# gyrotestbench.net
KiCad netlist of a schematic drawn in EAGLE
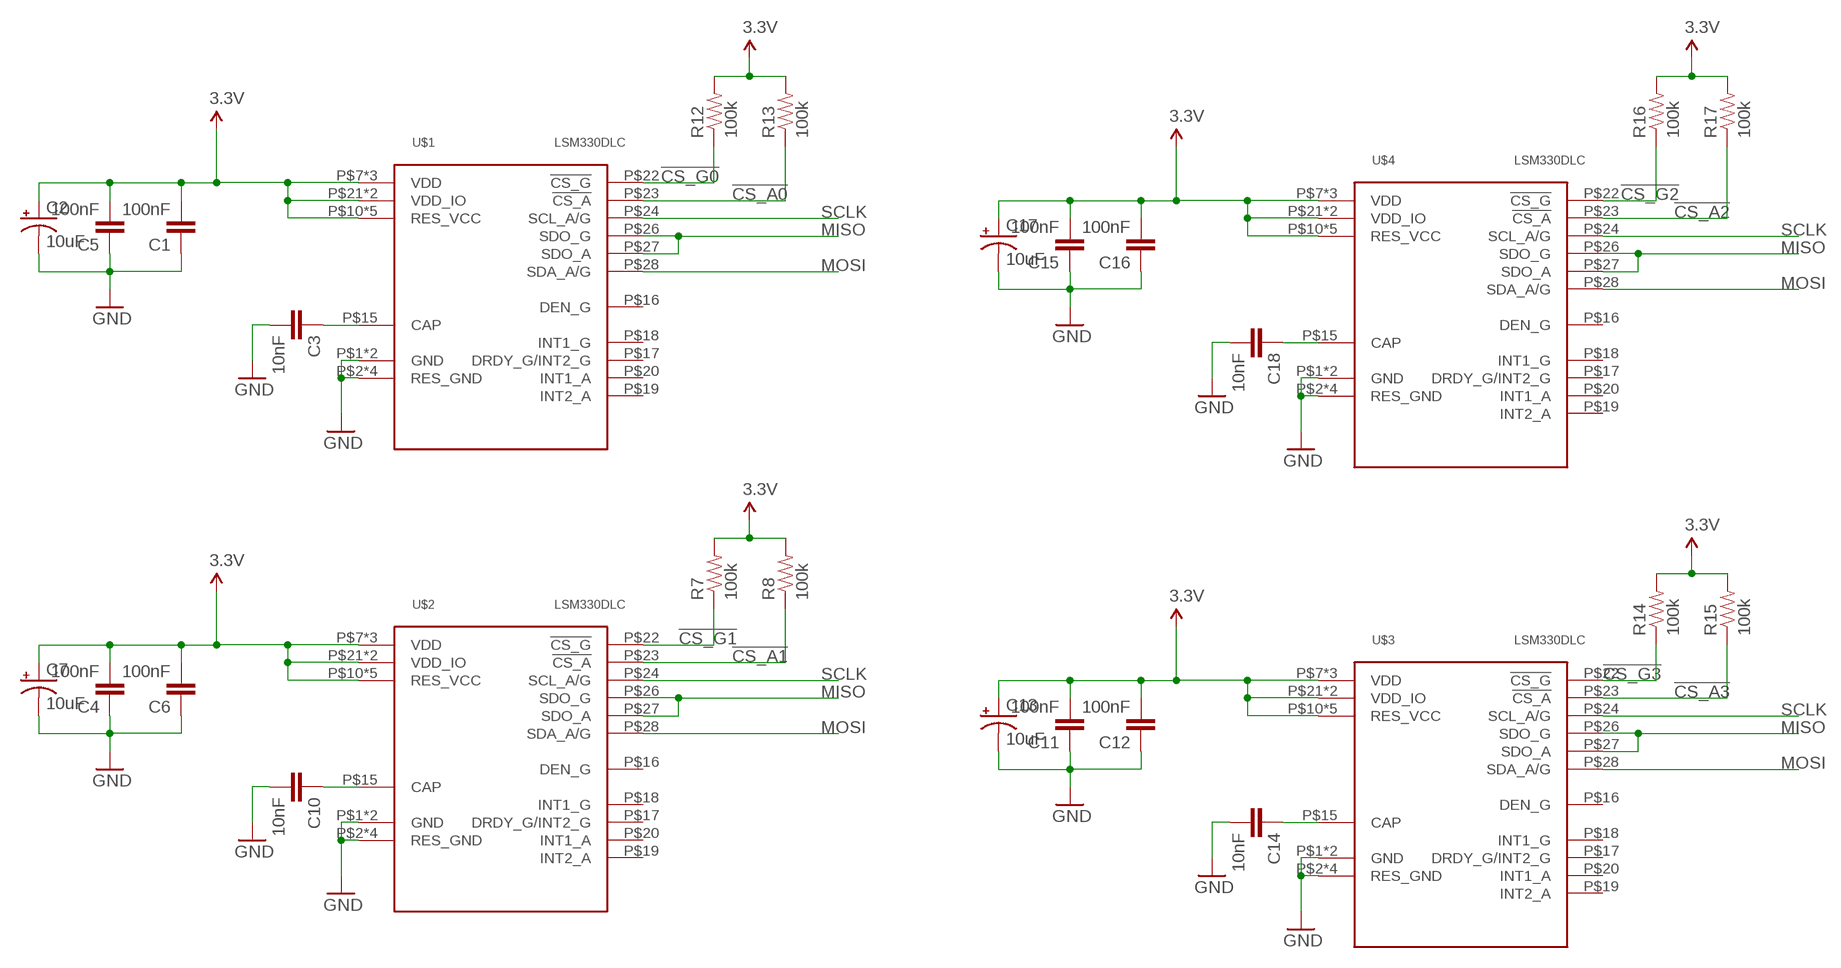
[diagram p0: schematic, sheet 1]
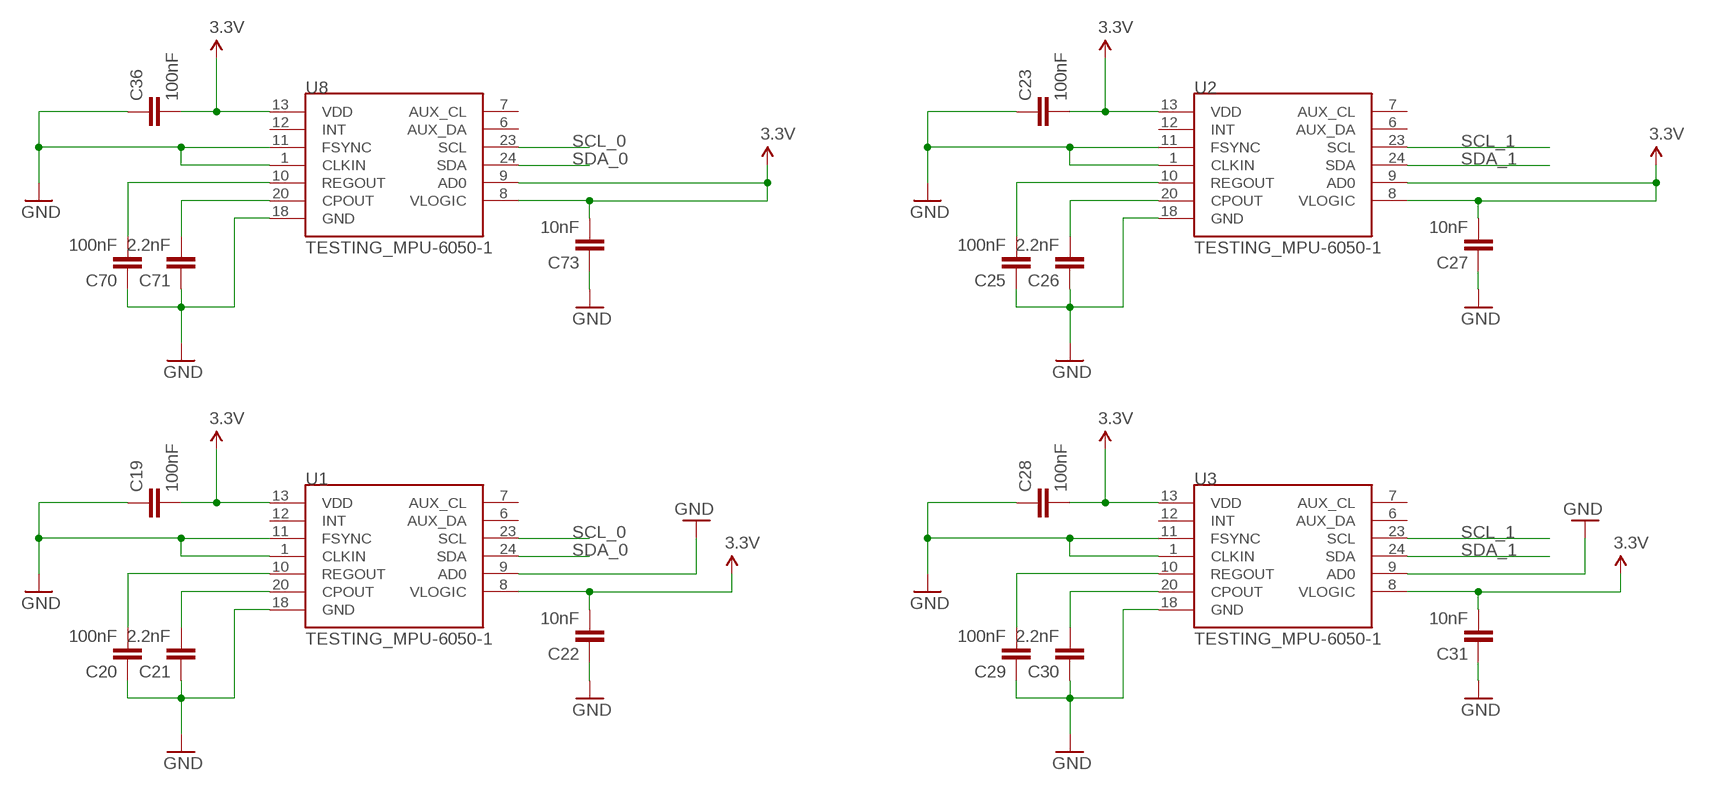
[diagram p1: schematic, sheet 2]
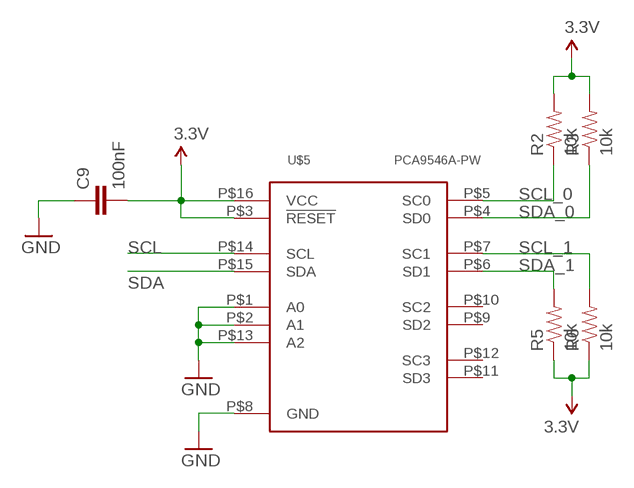
[diagram p2: schematic, sheet 3]
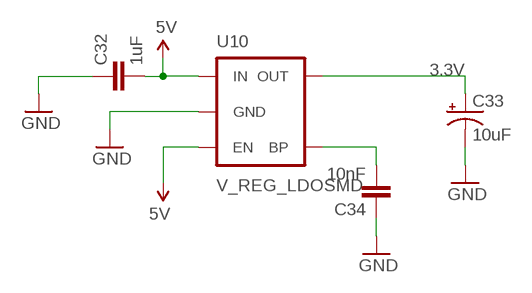
[diagram p3: schematic, sheet 4]
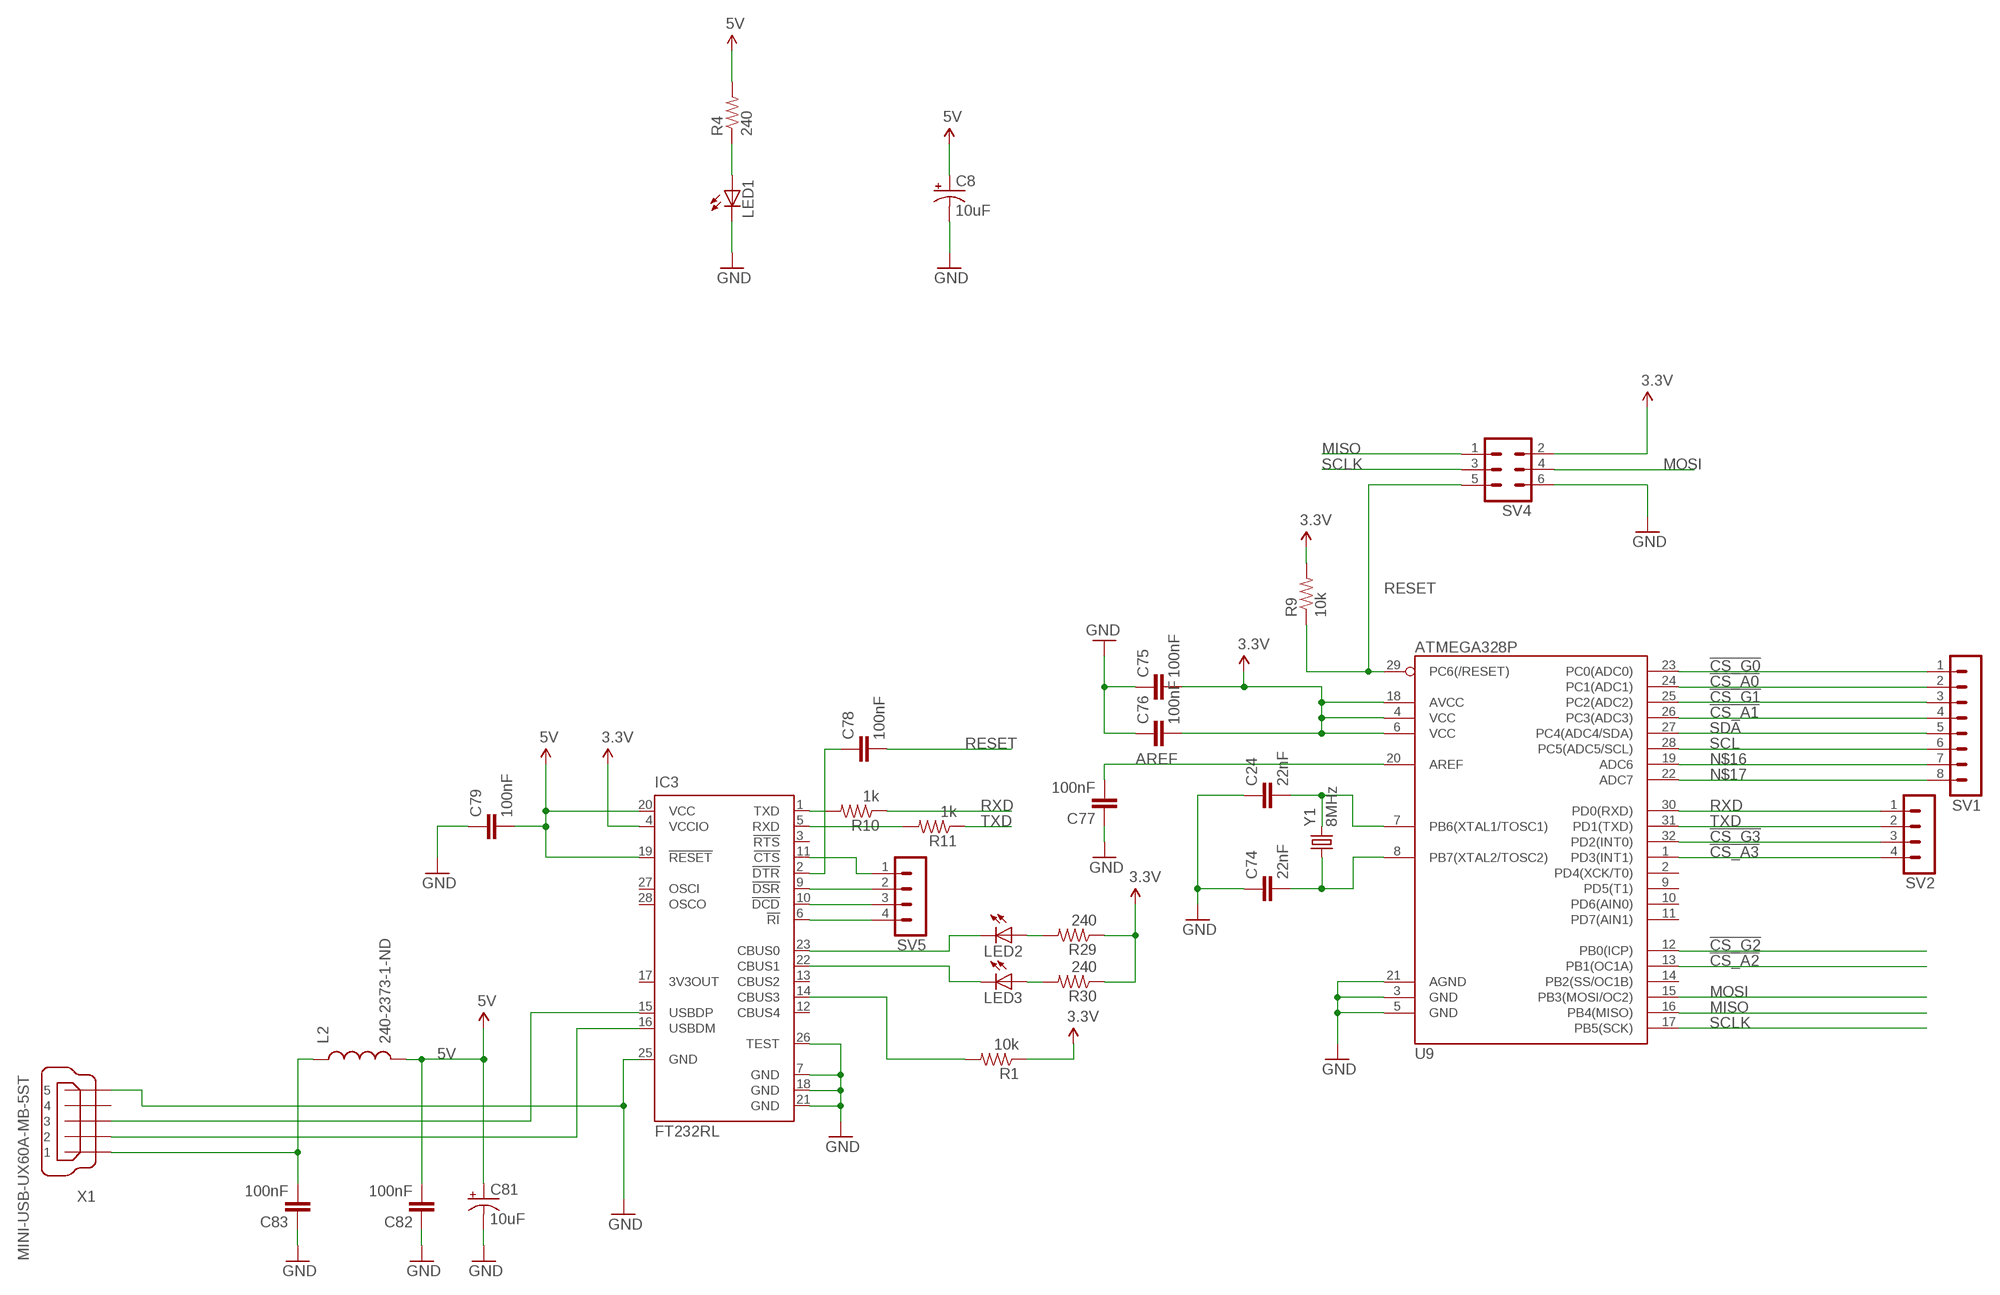
[diagram p4: schematic, sheet 5]

(export (version "E")
  (design (tool "Eeschema 10.0.6"))
  (components
    (comp (ref "C19")
      (value "100nF")
      (footprint "eagle-import:0603-CAP")
      (libsource (lib "eagle-import") (part "CAP0603-CAP"))
    )
    (comp (ref "C20")
      (value "100nF")
      (footprint "eagle-import:0603-CAP")
      (libsource (lib "eagle-import") (part "CAP0603-CAP"))
    )
    (comp (ref "C21")
      (value "2.2nF")
      (footprint "eagle-import:0603-CAP")
      (libsource (lib "eagle-import") (part "CAP0603-CAP"))
    )
    (comp (ref "C22")
      (value "10nF")
      (footprint "eagle-import:0603-CAP")
      (libsource (lib "eagle-import") (part "CAP0603-CAP"))
    )
    (comp (ref "C23")
      (value "100nF")
      (footprint "eagle-import:0603-CAP")
      (libsource (lib "eagle-import") (part "CAP0603-CAP"))
    )
    (comp (ref "C25")
      (value "100nF")
      (footprint "eagle-import:0603-CAP")
      (libsource (lib "eagle-import") (part "CAP0603-CAP"))
    )
    (comp (ref "C26")
      (value "2.2nF")
      (footprint "eagle-import:0603-CAP")
      (libsource (lib "eagle-import") (part "CAP0603-CAP"))
    )
    (comp (ref "C27")
      (value "10nF")
      (footprint "eagle-import:0603-CAP")
      (libsource (lib "eagle-import") (part "CAP0603-CAP"))
    )
    (comp (ref "C28")
      (value "100nF")
      (footprint "eagle-import:0603-CAP")
      (libsource (lib "eagle-import") (part "CAP0603-CAP"))
    )
    (comp (ref "C29")
      (value "100nF")
      (footprint "eagle-import:0603-CAP")
      (libsource (lib "eagle-import") (part "CAP0603-CAP"))
    )
    (comp (ref "C30")
      (value "2.2nF")
      (footprint "eagle-import:0603-CAP")
      (libsource (lib "eagle-import") (part "CAP0603-CAP"))
    )
    (comp (ref "C31")
      (value "10nF")
      (footprint "eagle-import:0603-CAP")
      (libsource (lib "eagle-import") (part "CAP0603-CAP"))
    )
    (comp (ref "C36")
      (value "100nF")
      (footprint "eagle-import:0603-CAP")
      (libsource (lib "eagle-import") (part "CAP0603-CAP"))
    )
    (comp (ref "C70")
      (value "100nF")
      (footprint "eagle-import:0603-CAP")
      (libsource (lib "eagle-import") (part "CAP0603-CAP"))
    )
    (comp (ref "C71")
      (value "2.2nF")
      (footprint "eagle-import:0603-CAP")
      (libsource (lib "eagle-import") (part "CAP0603-CAP"))
    )
    (comp (ref "C73")
      (value "10nF")
      (footprint "eagle-import:0603-CAP")
      (libsource (lib "eagle-import") (part "CAP0603-CAP"))
    )
    (comp (ref "U1")
      (value "TESTING_MPU-6050-1")
      (footprint "eagle-import:TESTING_QFN-24-4MM2")
      (libsource (lib "eagle-import") (part "TESTING_MPU-6050-1"))
    )
    (comp (ref "U2")
      (value "TESTING_MPU-6050-1")
      (footprint "eagle-import:TESTING_QFN-24-4MM2")
      (libsource (lib "eagle-import") (part "TESTING_MPU-6050-1"))
    )
    (comp (ref "U3")
      (value "TESTING_MPU-6050-1")
      (footprint "eagle-import:TESTING_QFN-24-4MM2")
      (libsource (lib "eagle-import") (part "TESTING_MPU-6050-1"))
    )
    (comp (ref "U8")
      (value "TESTING_MPU-6050-1")
      (footprint "eagle-import:TESTING_QFN-24-4MM2")
      (libsource (lib "eagle-import") (part "TESTING_MPU-6050-1"))
    )
    (comp (ref "C32")
      (value "1uF")
      (footprint "eagle-import:0603-CAP")
      (libsource (lib "eagle-import") (part "CAP0603-CAP"))
    )
    (comp (ref "C33")
      (value "10uF")
      (footprint "eagle-import:PANASONIC_B")
      (libsource (lib "eagle-import") (part "CPOL-USB"))
    )
    (comp (ref "C34")
      (value "10nF")
      (footprint "eagle-import:0603-CAP")
      (libsource (lib "eagle-import") (part "CAP0603-CAP"))
    )
    (comp (ref "U10")
      (value "V_REG_LDOSMD")
      (footprint "eagle-import:SOT23-5")
      (libsource (lib "eagle-import") (part "V_REG_LDOSMD"))
    )
    (comp (ref "C1")
      (value "100nF")
      (footprint "eagle-import:0603-CAP")
      (libsource (lib "eagle-import") (part "CAP0603-CAP"))
    )
    (comp (ref "C2")
      (value "10uF")
      (footprint "eagle-import:PANASONIC_B")
      (libsource (lib "eagle-import") (part "CPOL-USB"))
    )
    (comp (ref "C3")
      (value "10nF")
      (footprint "eagle-import:0603-CAP")
      (libsource (lib "eagle-import") (part "CAP0603-CAP"))
    )
    (comp (ref "C4")
      (value "100nF")
      (footprint "eagle-import:0603-CAP")
      (libsource (lib "eagle-import") (part "CAP0603-CAP"))
    )
    (comp (ref "C5")
      (value "100nF")
      (footprint "eagle-import:0603-CAP")
      (libsource (lib "eagle-import") (part "CAP0603-CAP"))
    )
    (comp (ref "C6")
      (value "100nF")
      (footprint "eagle-import:0603-CAP")
      (libsource (lib "eagle-import") (part "CAP0603-CAP"))
    )
    (comp (ref "C7")
      (value "10uF")
      (footprint "eagle-import:PANASONIC_B")
      (libsource (lib "eagle-import") (part "CPOL-USB"))
    )
    (comp (ref "C10")
      (value "10nF")
      (footprint "eagle-import:0603-CAP")
      (libsource (lib "eagle-import") (part "CAP0603-CAP"))
    )
    (comp (ref "C11")
      (value "100nF")
      (footprint "eagle-import:0603-CAP")
      (libsource (lib "eagle-import") (part "CAP0603-CAP"))
    )
    (comp (ref "C12")
      (value "100nF")
      (footprint "eagle-import:0603-CAP")
      (libsource (lib "eagle-import") (part "CAP0603-CAP"))
    )
    (comp (ref "C13")
      (value "10uF")
      (footprint "eagle-import:PANASONIC_B")
      (libsource (lib "eagle-import") (part "CPOL-USB"))
    )
    (comp (ref "C14")
      (value "10nF")
      (footprint "eagle-import:0603-CAP")
      (libsource (lib "eagle-import") (part "CAP0603-CAP"))
    )
    (comp (ref "C15")
      (value "100nF")
      (footprint "eagle-import:0603-CAP")
      (libsource (lib "eagle-import") (part "CAP0603-CAP"))
    )
    (comp (ref "C16")
      (value "100nF")
      (footprint "eagle-import:0603-CAP")
      (libsource (lib "eagle-import") (part "CAP0603-CAP"))
    )
    (comp (ref "C17")
      (value "10uF")
      (footprint "eagle-import:PANASONIC_B")
      (libsource (lib "eagle-import") (part "CPOL-USB"))
    )
    (comp (ref "C18")
      (value "10nF")
      (footprint "eagle-import:0603-CAP")
      (libsource (lib "eagle-import") (part "CAP0603-CAP"))
    )
    (comp (ref "R7")
      (value "100k")
      (footprint "eagle-import:0603-RES")
      (libsource (lib "eagle-import") (part "RESISTOR0603-RES"))
    )
    (comp (ref "R8")
      (value "100k")
      (footprint "eagle-import:0603-RES")
      (libsource (lib "eagle-import") (part "RESISTOR0603-RES"))
    )
    (comp (ref "R12")
      (value "100k")
      (footprint "eagle-import:0603-RES")
      (libsource (lib "eagle-import") (part "RESISTOR0603-RES"))
    )
    (comp (ref "R13")
      (value "100k")
      (footprint "eagle-import:0603-RES")
      (libsource (lib "eagle-import") (part "RESISTOR0603-RES"))
    )
    (comp (ref "R14")
      (value "100k")
      (footprint "eagle-import:0603-RES")
      (libsource (lib "eagle-import") (part "RESISTOR0603-RES"))
    )
    (comp (ref "R15")
      (value "100k")
      (footprint "eagle-import:0603-RES")
      (libsource (lib "eagle-import") (part "RESISTOR0603-RES"))
    )
    (comp (ref "R16")
      (value "100k")
      (footprint "eagle-import:0603-RES")
      (libsource (lib "eagle-import") (part "RESISTOR0603-RES"))
    )
    (comp (ref "R17")
      (value "100k")
      (footprint "eagle-import:0603-RES")
      (libsource (lib "eagle-import") (part "RESISTOR0603-RES"))
    )
    (comp (ref "U$1")
      (value "LSM330DLC")
      (footprint "eagle-import:LGA-28")
      (libsource (lib "eagle-import") (part "LSM330DLC"))
    )
    (comp (ref "U$2")
      (value "LSM330DLC")
      (footprint "eagle-import:LGA-28")
      (libsource (lib "eagle-import") (part "LSM330DLC"))
    )
    (comp (ref "U$3")
      (value "LSM330DLC")
      (footprint "eagle-import:LGA-28")
      (libsource (lib "eagle-import") (part "LSM330DLC"))
    )
    (comp (ref "U$4")
      (value "LSM330DLC")
      (footprint "eagle-import:LGA-28")
      (libsource (lib "eagle-import") (part "LSM330DLC"))
    )
    (comp (ref "C8")
      (value "10uF")
      (footprint "eagle-import:PANASONIC_B")
      (libsource (lib "eagle-import") (part "CPOL-USB"))
    )
    (comp (ref "C24")
      (value "22nF")
      (footprint "eagle-import:0603-CAP")
      (libsource (lib "eagle-import") (part "CAP0603-CAP"))
    )
    (comp (ref "C74")
      (value "22nF")
      (footprint "eagle-import:0603-CAP")
      (libsource (lib "eagle-import") (part "CAP0603-CAP"))
    )
    (comp (ref "C75")
      (value "100nF")
      (footprint "eagle-import:0603-CAP")
      (libsource (lib "eagle-import") (part "CAP0603-CAP"))
    )
    (comp (ref "C76")
      (value "100nF")
      (footprint "eagle-import:0603-CAP")
      (libsource (lib "eagle-import") (part "CAP0603-CAP"))
    )
    (comp (ref "C77")
      (value "100nF")
      (footprint "eagle-import:0603-CAP")
      (libsource (lib "eagle-import") (part "CAP0603-CAP"))
    )
    (comp (ref "C78")
      (value "100nF")
      (footprint "eagle-import:0603-CAP")
      (libsource (lib "eagle-import") (part "CAP0603-CAP"))
    )
    (comp (ref "C79")
      (value "100nF")
      (footprint "eagle-import:0603-CAP")
      (libsource (lib "eagle-import") (part "CAP0603-CAP"))
    )
    (comp (ref "C81")
      (value "10uF")
      (footprint "eagle-import:PANASONIC_B")
      (libsource (lib "eagle-import") (part "CPOL-USB"))
    )
    (comp (ref "C82")
      (value "100nF")
      (footprint "eagle-import:0603-CAP")
      (libsource (lib "eagle-import") (part "CAP0603-CAP"))
    )
    (comp (ref "C83")
      (value "100nF")
      (footprint "eagle-import:0603-CAP")
      (libsource (lib "eagle-import") (part "CAP0603-CAP"))
    )
    (comp (ref "IC3")
      (value "FT232RL")
      (footprint "eagle-import:SSOP28")
      (libsource (lib "eagle-import") (part "FT232RL"))
    )
    (comp (ref "L2")
      (value "240-2373-1-ND")
      (footprint "eagle-import:0603")
      (libsource (lib "eagle-import") (part "INDUCTOR0603"))
    )
    (comp (ref "LED1")
      (value "LED0603")
      (footprint "eagle-import:LED-0603")
      (libsource (lib "eagle-import") (part "LED0603"))
    )
    (comp (ref "LED2")
      (value "LED0603")
      (footprint "eagle-import:LED-0603")
      (libsource (lib "eagle-import") (part "LED0603"))
    )
    (comp (ref "LED3")
      (value "LED0603")
      (footprint "eagle-import:LED-0603")
      (libsource (lib "eagle-import") (part "LED0603"))
    )
    (comp (ref "R1")
      (value "10k")
      (footprint "eagle-import:0603-RES")
      (libsource (lib "eagle-import") (part "RESISTOR0603-RES"))
    )
    (comp (ref "R4")
      (value "240")
      (footprint "eagle-import:0603-RES")
      (libsource (lib "eagle-import") (part "RESISTOR0603-RES"))
    )
    (comp (ref "R9")
      (value "10k")
      (footprint "eagle-import:0603-RES")
      (libsource (lib "eagle-import") (part "RESISTOR0603-RES"))
    )
    (comp (ref "R10")
      (value "1k")
      (footprint "eagle-import:0603-RES")
      (libsource (lib "eagle-import") (part "RESISTOR0603-RES"))
    )
    (comp (ref "R11")
      (value "1k")
      (footprint "eagle-import:0603-RES")
      (libsource (lib "eagle-import") (part "RESISTOR0603-RES"))
    )
    (comp (ref "R29")
      (value "240")
      (footprint "eagle-import:0603-RES")
      (libsource (lib "eagle-import") (part "RESISTOR0603-RES"))
    )
    (comp (ref "R30")
      (value "240")
      (footprint "eagle-import:0603-RES")
      (libsource (lib "eagle-import") (part "RESISTOR0603-RES"))
    )
    (comp (ref "SV1")
      (value "MA08-1")
      (footprint "eagle-import:MA08-1")
      (libsource (lib "eagle-import") (part "MA08-1"))
    )
    (comp (ref "SV2")
      (value "MA04-1")
      (footprint "eagle-import:MA04-1")
      (fields (field (name "OC_FARNELL") "unknown") (field (name "OC_NEWARK") "unknown"))
      (libsource (lib "eagle-import") (part "MA04-1"))
    )
    (comp (ref "SV4")
      (value "MA03-2")
      (footprint "eagle-import:MA03-2")
      (libsource (lib "eagle-import") (part "MA03-2"))
    )
    (comp (ref "SV5")
      (value "MA04-1")
      (footprint "eagle-import:MA04-1")
      (libsource (lib "eagle-import") (part "MA04-1"))
    )
    (comp (ref "U9")
      (value "ATMEGA328P")
      (footprint "eagle-import:TQFP32-08")
      (libsource (lib "eagle-import") (part "ATMEGA328_SMT"))
    )
    (comp (ref "X1")
      (value "MINI-USB-UX60A-MB-5ST")
      (footprint "eagle-import:UX60A-MB-5ST")
      (libsource (lib "eagle-import") (part "MINI-USB-UX60A-MB-5ST"))
    )
    (comp (ref "Y1")
      (value "8MHz")
      (footprint "eagle-import:HC49US")
      (libsource (lib "eagle-import") (part "CRYSTALHC49US"))
    )
    (comp (ref "C9")
      (value "100nF")
      (footprint "eagle-import:0603-CAP")
      (libsource (lib "eagle-import") (part "CAP0603-CAP"))
    )
    (comp (ref "R2")
      (value "10k")
      (footprint "eagle-import:0603-RES")
      (libsource (lib "eagle-import") (part "RESISTOR0603-RES"))
    )
    (comp (ref "R3")
      (value "10k")
      (footprint "eagle-import:0603-RES")
      (libsource (lib "eagle-import") (part "RESISTOR0603-RES"))
    )
    (comp (ref "R5")
      (value "10k")
      (footprint "eagle-import:0603-RES")
      (libsource (lib "eagle-import") (part "RESISTOR0603-RES"))
    )
    (comp (ref "R6")
      (value "10k")
      (footprint "eagle-import:0603-RES")
      (libsource (lib "eagle-import") (part "RESISTOR0603-RES"))
    )
    (comp (ref "U$5")
      (value "PCA9546A-PW")
      (footprint "eagle-import:TSSOP-16")
      (libsource (lib "eagle-import") (part "PCA9546A-PW"))
    )
  )
  (nets
    (net (code "1") (name "3.3V") (class "Default")
      (node (ref "C1") (pin "2") (pinfunction "2_2") (pintype "passive"))
      (node (ref "C11") (pin "2") (pinfunction "2_2") (pintype "passive"))
      (node (ref "C12") (pin "2") (pinfunction "2_2") (pintype "passive"))
      (node (ref "C13") (pin "+") (pinfunction "+_+") (pintype "passive"))
      (node (ref "C15") (pin "2") (pinfunction "2_2") (pintype "passive"))
      (node (ref "C16") (pin "2") (pinfunction "2_2") (pintype "passive"))
      (node (ref "C17") (pin "+") (pinfunction "+_+") (pintype "passive"))
      (node (ref "C19") (pin "2") (pinfunction "2_2") (pintype "passive"))
      (node (ref "C2") (pin "+") (pinfunction "+_+") (pintype "passive"))
      (node (ref "C22") (pin "2") (pinfunction "2_2") (pintype "passive"))
      (node (ref "C23") (pin "2") (pinfunction "2_2") (pintype "passive"))
      (node (ref "C27") (pin "2") (pinfunction "2_2") (pintype "passive"))
      (node (ref "C28") (pin "2") (pinfunction "2_2") (pintype "passive"))
      (node (ref "C31") (pin "2") (pinfunction "2_2") (pintype "passive"))
      (node (ref "C33") (pin "+") (pinfunction "+_+") (pintype "passive"))
      (node (ref "C36") (pin "2") (pinfunction "2_2") (pintype "passive"))
      (node (ref "C4") (pin "2") (pinfunction "2_2") (pintype "passive"))
      (node (ref "C5") (pin "2") (pinfunction "2_2") (pintype "passive"))
      (node (ref "C6") (pin "2") (pinfunction "2_2") (pintype "passive"))
      (node (ref "C7") (pin "+") (pinfunction "+_+") (pintype "passive"))
      (node (ref "C73") (pin "2") (pinfunction "2_2") (pintype "passive"))
      (node (ref "C75") (pin "2") (pinfunction "2_2") (pintype "passive"))
      (node (ref "C76") (pin "2") (pinfunction "2_2") (pintype "passive"))
      (node (ref "C9") (pin "2") (pinfunction "2_2") (pintype "passive"))
      (node (ref "IC3") (pin "4") (pinfunction "VCCIO_4") (pintype "power_in"))
      (node (ref "R1") (pin "1") (pinfunction "1_1") (pintype "passive"))
      (node (ref "R12") (pin "2") (pinfunction "2_2") (pintype "passive"))
      (node (ref "R13") (pin "2") (pinfunction "2_2") (pintype "passive"))
      (node (ref "R14") (pin "2") (pinfunction "2_2") (pintype "passive"))
      (node (ref "R15") (pin "2") (pinfunction "2_2") (pintype "passive"))
      (node (ref "R16") (pin "2") (pinfunction "2_2") (pintype "passive"))
      (node (ref "R17") (pin "2") (pinfunction "2_2") (pintype "passive"))
      (node (ref "R2") (pin "2") (pinfunction "2_2") (pintype "passive"))
      (node (ref "R29") (pin "1") (pinfunction "1_1") (pintype "passive"))
      (node (ref "R3") (pin "2") (pinfunction "2_2") (pintype "passive"))
      (node (ref "R30") (pin "1") (pinfunction "1_1") (pintype "passive"))
      (node (ref "R5") (pin "1") (pinfunction "1_1") (pintype "passive"))
      (node (ref "R6") (pin "1") (pinfunction "1_1") (pintype "passive"))
      (node (ref "R7") (pin "2") (pinfunction "2_2") (pintype "passive"))
      (node (ref "R8") (pin "2") (pinfunction "2_2") (pintype "passive"))
      (node (ref "R9") (pin "2") (pinfunction "2_2") (pintype "passive"))
      (node (ref "SV4") (pin "2") (pinfunction "2_2") (pintype "passive"))
      (node (ref "U$1") (pin "P$10") (pinfunction "RES_VCC_P$10") (pintype "bidirectional"))
      (node (ref "U$1") (pin "P$11") (pinfunction "RES_VCC_P$11") (pintype "bidirectional"))
      (node (ref "U$1") (pin "P$12") (pinfunction "RES_VCC_P$12") (pintype "bidirectional"))
      (node (ref "U$1") (pin "P$13") (pinfunction "RES_VCC_P$13") (pintype "bidirectional"))
      (node (ref "U$1") (pin "P$14") (pinfunction "RES_VCC_P$14") (pintype "bidirectional"))
      (node (ref "U$1") (pin "P$21") (pinfunction "VDD_IO_P$21") (pintype "bidirectional"))
      (node (ref "U$1") (pin "P$25") (pinfunction "VDD_IO_P$25") (pintype "bidirectional"))
      (node (ref "U$1") (pin "P$7") (pinfunction "VDD_P$7") (pintype "bidirectional"))
      (node (ref "U$1") (pin "P$8") (pinfunction "VDD_P$8") (pintype "bidirectional"))
      (node (ref "U$1") (pin "P$9") (pinfunction "VDD_P$9") (pintype "bidirectional"))
      (node (ref "U$2") (pin "P$10") (pinfunction "RES_VCC_P$10") (pintype "bidirectional"))
      (node (ref "U$2") (pin "P$11") (pinfunction "RES_VCC_P$11") (pintype "bidirectional"))
      (node (ref "U$2") (pin "P$12") (pinfunction "RES_VCC_P$12") (pintype "bidirectional"))
      (node (ref "U$2") (pin "P$13") (pinfunction "RES_VCC_P$13") (pintype "bidirectional"))
      (node (ref "U$2") (pin "P$14") (pinfunction "RES_VCC_P$14") (pintype "bidirectional"))
      (node (ref "U$2") (pin "P$21") (pinfunction "VDD_IO_P$21") (pintype "bidirectional"))
      (node (ref "U$2") (pin "P$25") (pinfunction "VDD_IO_P$25") (pintype "bidirectional"))
      (node (ref "U$2") (pin "P$7") (pinfunction "VDD_P$7") (pintype "bidirectional"))
      (node (ref "U$2") (pin "P$8") (pinfunction "VDD_P$8") (pintype "bidirectional"))
      (node (ref "U$2") (pin "P$9") (pinfunction "VDD_P$9") (pintype "bidirectional"))
      (node (ref "U$3") (pin "P$10") (pinfunction "RES_VCC_P$10") (pintype "bidirectional"))
      (node (ref "U$3") (pin "P$11") (pinfunction "RES_VCC_P$11") (pintype "bidirectional"))
      (node (ref "U$3") (pin "P$12") (pinfunction "RES_VCC_P$12") (pintype "bidirectional"))
      (node (ref "U$3") (pin "P$13") (pinfunction "RES_VCC_P$13") (pintype "bidirectional"))
      (node (ref "U$3") (pin "P$14") (pinfunction "RES_VCC_P$14") (pintype "bidirectional"))
      (node (ref "U$3") (pin "P$21") (pinfunction "VDD_IO_P$21") (pintype "bidirectional"))
      (node (ref "U$3") (pin "P$25") (pinfunction "VDD_IO_P$25") (pintype "bidirectional"))
      (node (ref "U$3") (pin "P$7") (pinfunction "VDD_P$7") (pintype "bidirectional"))
      (node (ref "U$3") (pin "P$8") (pinfunction "VDD_P$8") (pintype "bidirectional"))
      (node (ref "U$3") (pin "P$9") (pinfunction "VDD_P$9") (pintype "bidirectional"))
      (node (ref "U$4") (pin "P$10") (pinfunction "RES_VCC_P$10") (pintype "bidirectional"))
      (node (ref "U$4") (pin "P$11") (pinfunction "RES_VCC_P$11") (pintype "bidirectional"))
      (node (ref "U$4") (pin "P$12") (pinfunction "RES_VCC_P$12") (pintype "bidirectional"))
      (node (ref "U$4") (pin "P$13") (pinfunction "RES_VCC_P$13") (pintype "bidirectional"))
      (node (ref "U$4") (pin "P$14") (pinfunction "RES_VCC_P$14") (pintype "bidirectional"))
      (node (ref "U$4") (pin "P$21") (pinfunction "VDD_IO_P$21") (pintype "bidirectional"))
      (node (ref "U$4") (pin "P$25") (pinfunction "VDD_IO_P$25") (pintype "bidirectional"))
      (node (ref "U$4") (pin "P$7") (pinfunction "VDD_P$7") (pintype "bidirectional"))
      (node (ref "U$4") (pin "P$8") (pinfunction "VDD_P$8") (pintype "bidirectional"))
      (node (ref "U$4") (pin "P$9") (pinfunction "VDD_P$9") (pintype "bidirectional"))
      (node (ref "U$5") (pin "P$16") (pinfunction "VCC_P$16") (pintype "bidirectional"))
      (node (ref "U$5") (pin "P$3") (pinfunction "~{RESET}_P$3") (pintype "bidirectional"))
      (node (ref "U1") (pin "13") (pinfunction "VDD_13") (pintype "bidirectional"))
      (node (ref "U1") (pin "8") (pinfunction "VLOGIC_8") (pintype "bidirectional"))
      (node (ref "U10") (pin "5") (pinfunction "OUT_5") (pintype "passive"))
      (node (ref "U2") (pin "13") (pinfunction "VDD_13") (pintype "bidirectional"))
      (node (ref "U2") (pin "8") (pinfunction "VLOGIC_8") (pintype "bidirectional"))
      (node (ref "U2") (pin "9") (pinfunction "AD0_9") (pintype "bidirectional"))
      (node (ref "U3") (pin "13") (pinfunction "VDD_13") (pintype "bidirectional"))
      (node (ref "U3") (pin "8") (pinfunction "VLOGIC_8") (pintype "bidirectional"))
      (node (ref "U8") (pin "13") (pinfunction "VDD_13") (pintype "bidirectional"))
      (node (ref "U8") (pin "8") (pinfunction "VLOGIC_8") (pintype "bidirectional"))
      (node (ref "U8") (pin "9") (pinfunction "AD0_9") (pintype "bidirectional"))
      (node (ref "U9") (pin "18") (pinfunction "AVCC_18") (pintype "bidirectional"))
      (node (ref "U9") (pin "4") (pinfunction "VCC_4") (pintype "bidirectional"))
      (node (ref "U9") (pin "6") (pinfunction "VCC_6") (pintype "bidirectional"))
    )
    (net (code "2") (name "5V") (class "Default")
      (node (ref "C32") (pin "2") (pinfunction "2_2") (pintype "passive"))
      (node (ref "C79") (pin "2") (pinfunction "2_2") (pintype "passive"))
      (node (ref "C8") (pin "+") (pinfunction "+_+") (pintype "passive"))
      (node (ref "C81") (pin "+") (pinfunction "+_+") (pintype "passive"))
      (node (ref "C82") (pin "2") (pinfunction "2_2") (pintype "passive"))
      (node (ref "IC3") (pin "19") (pinfunction "~{RESET}_19") (pintype "input"))
      (node (ref "IC3") (pin "20") (pinfunction "VCC_20") (pintype "power_in"))
      (node (ref "L2") (pin "2") (pinfunction "2_2") (pintype "passive"))
      (node (ref "R4") (pin "2") (pinfunction "2_2") (pintype "passive"))
      (node (ref "U10") (pin "1") (pinfunction "IN_1") (pintype "input"))
      (node (ref "U10") (pin "3") (pinfunction "EN_3") (pintype "input"))
    )
    (net (code "3") (name "AREF") (class "Default")
      (node (ref "C77") (pin "2") (pinfunction "2_2") (pintype "passive"))
      (node (ref "U9") (pin "20") (pinfunction "AREF_20") (pintype "bidirectional"))
    )
    (net (code "4") (name "GND") (class "Default")
      (node (ref "C1") (pin "1") (pinfunction "1_1") (pintype "passive"))
      (node (ref "C10") (pin "2") (pinfunction "2_2") (pintype "passive"))
      (node (ref "C11") (pin "1") (pinfunction "1_1") (pintype "passive"))
      (node (ref "C12") (pin "1") (pinfunction "1_1") (pintype "passive"))
      (node (ref "C13") (pin "-") (pinfunction "-_-") (pintype "passive"))
      (node (ref "C14") (pin "2") (pinfunction "2_2") (pintype "passive"))
      (node (ref "C15") (pin "1") (pinfunction "1_1") (pintype "passive"))
      (node (ref "C16") (pin "1") (pinfunction "1_1") (pintype "passive"))
      (node (ref "C17") (pin "-") (pinfunction "-_-") (pintype "passive"))
      (node (ref "C18") (pin "2") (pinfunction "2_2") (pintype "passive"))
      (node (ref "C19") (pin "1") (pinfunction "1_1") (pintype "passive"))
      (node (ref "C2") (pin "-") (pinfunction "-_-") (pintype "passive"))
      (node (ref "C20") (pin "1") (pinfunction "1_1") (pintype "passive"))
      (node (ref "C21") (pin "1") (pinfunction "1_1") (pintype "passive"))
      (node (ref "C22") (pin "1") (pinfunction "1_1") (pintype "passive"))
      (node (ref "C23") (pin "1") (pinfunction "1_1") (pintype "passive"))
      (node (ref "C24") (pin "1") (pinfunction "1_1") (pintype "passive"))
      (node (ref "C25") (pin "1") (pinfunction "1_1") (pintype "passive"))
      (node (ref "C26") (pin "1") (pinfunction "1_1") (pintype "passive"))
      (node (ref "C27") (pin "1") (pinfunction "1_1") (pintype "passive"))
      (node (ref "C28") (pin "1") (pinfunction "1_1") (pintype "passive"))
      (node (ref "C29") (pin "1") (pinfunction "1_1") (pintype "passive"))
      (node (ref "C3") (pin "2") (pinfunction "2_2") (pintype "passive"))
      (node (ref "C30") (pin "1") (pinfunction "1_1") (pintype "passive"))
      (node (ref "C31") (pin "1") (pinfunction "1_1") (pintype "passive"))
      (node (ref "C32") (pin "1") (pinfunction "1_1") (pintype "passive"))
      (node (ref "C33") (pin "-") (pinfunction "-_-") (pintype "passive"))
      (node (ref "C34") (pin "1") (pinfunction "1_1") (pintype "passive"))
      (node (ref "C36") (pin "1") (pinfunction "1_1") (pintype "passive"))
      (node (ref "C4") (pin "1") (pinfunction "1_1") (pintype "passive"))
      (node (ref "C5") (pin "1") (pinfunction "1_1") (pintype "passive"))
      (node (ref "C6") (pin "1") (pinfunction "1_1") (pintype "passive"))
      (node (ref "C7") (pin "-") (pinfunction "-_-") (pintype "passive"))
      (node (ref "C70") (pin "1") (pinfunction "1_1") (pintype "passive"))
      (node (ref "C71") (pin "1") (pinfunction "1_1") (pintype "passive"))
      (node (ref "C73") (pin "1") (pinfunction "1_1") (pintype "passive"))
      (node (ref "C74") (pin "1") (pinfunction "1_1") (pintype "passive"))
      (node (ref "C75") (pin "1") (pinfunction "1_1") (pintype "passive"))
      (node (ref "C76") (pin "1") (pinfunction "1_1") (pintype "passive"))
      (node (ref "C77") (pin "1") (pinfunction "1_1") (pintype "passive"))
      (node (ref "C79") (pin "1") (pinfunction "1_1") (pintype "passive"))
      (node (ref "C8") (pin "-") (pinfunction "-_-") (pintype "passive"))
      (node (ref "C81") (pin "-") (pinfunction "-_-") (pintype "passive"))
      (node (ref "C82") (pin "1") (pinfunction "1_1") (pintype "passive"))
      (node (ref "C83") (pin "1") (pinfunction "1_1") (pintype "passive"))
      (node (ref "C9") (pin "1") (pinfunction "1_1") (pintype "passive"))
      (node (ref "IC3") (pin "18") (pinfunction "GND_18") (pintype "power_in"))
      (node (ref "IC3") (pin "21") (pinfunction "GND_21") (pintype "power_in"))
      (node (ref "IC3") (pin "25") (pinfunction "GND_25") (pintype "power_in"))
      (node (ref "IC3") (pin "26") (pinfunction "TEST_26") (pintype "input"))
      (node (ref "IC3") (pin "7") (pinfunction "GND_7") (pintype "power_in"))
      (node (ref "LED1") (pin "C") (pinfunction "C_C") (pintype "passive"))
      (node (ref "SV4") (pin "6") (pinfunction "6_6") (pintype "passive"))
      (node (ref "U$1") (pin "P$1") (pinfunction "GND_P$1") (pintype "bidirectional"))
      (node (ref "U$1") (pin "P$2") (pinfunction "RES_GND_P$2") (pintype "bidirectional"))
      (node (ref "U$1") (pin "P$3") (pinfunction "RES_GND_P$3") (pintype "bidirectional"))
      (node (ref "U$1") (pin "P$4") (pinfunction "RES_GND_P$4") (pintype "bidirectional"))
      (node (ref "U$1") (pin "P$5") (pinfunction "RES_GND_P$5") (pintype "bidirectional"))
      (node (ref "U$1") (pin "P$6") (pinfunction "GND_P$6") (pintype "bidirectional"))
      (node (ref "U$2") (pin "P$1") (pinfunction "GND_P$1") (pintype "bidirectional"))
      (node (ref "U$2") (pin "P$2") (pinfunction "RES_GND_P$2") (pintype "bidirectional"))
      (node (ref "U$2") (pin "P$3") (pinfunction "RES_GND_P$3") (pintype "bidirectional"))
      (node (ref "U$2") (pin "P$4") (pinfunction "RES_GND_P$4") (pintype "bidirectional"))
      (node (ref "U$2") (pin "P$5") (pinfunction "RES_GND_P$5") (pintype "bidirectional"))
      (node (ref "U$2") (pin "P$6") (pinfunction "GND_P$6") (pintype "bidirectional"))
      (node (ref "U$3") (pin "P$1") (pinfunction "GND_P$1") (pintype "bidirectional"))
      (node (ref "U$3") (pin "P$2") (pinfunction "RES_GND_P$2") (pintype "bidirectional"))
      (node (ref "U$3") (pin "P$3") (pinfunction "RES_GND_P$3") (pintype "bidirectional"))
      (node (ref "U$3") (pin "P$4") (pinfunction "RES_GND_P$4") (pintype "bidirectional"))
      (node (ref "U$3") (pin "P$5") (pinfunction "RES_GND_P$5") (pintype "bidirectional"))
      (node (ref "U$3") (pin "P$6") (pinfunction "GND_P$6") (pintype "bidirectional"))
      (node (ref "U$4") (pin "P$1") (pinfunction "GND_P$1") (pintype "bidirectional"))
      (node (ref "U$4") (pin "P$2") (pinfunction "RES_GND_P$2") (pintype "bidirectional"))
      (node (ref "U$4") (pin "P$3") (pinfunction "RES_GND_P$3") (pintype "bidirectional"))
      (node (ref "U$4") (pin "P$4") (pinfunction "RES_GND_P$4") (pintype "bidirectional"))
      (node (ref "U$4") (pin "P$5") (pinfunction "RES_GND_P$5") (pintype "bidirectional"))
      (node (ref "U$4") (pin "P$6") (pinfunction "GND_P$6") (pintype "bidirectional"))
      (node (ref "U$5") (pin "P$1") (pinfunction "A0_P$1") (pintype "bidirectional"))
      (node (ref "U$5") (pin "P$13") (pinfunction "A2_P$13") (pintype "bidirectional"))
      (node (ref "U$5") (pin "P$2") (pinfunction "A1_P$2") (pintype "bidirectional"))
      (node (ref "U$5") (pin "P$8") (pinfunction "GND_P$8") (pintype "bidirectional"))
      (node (ref "U1") (pin "1") (pinfunction "CLKIN_1") (pintype "bidirectional"))
      (node (ref "U1") (pin "11") (pinfunction "FSYNC_11") (pintype "bidirectional"))
      (node (ref "U1") (pin "18") (pinfunction "GND_18") (pintype "bidirectional"))
      (node (ref "U1") (pin "9") (pinfunction "AD0_9") (pintype "bidirectional"))
      (node (ref "U10") (pin "2") (pinfunction "GND_2") (pintype "input"))
      (node (ref "U2") (pin "1") (pinfunction "CLKIN_1") (pintype "bidirectional"))
      (node (ref "U2") (pin "11") (pinfunction "FSYNC_11") (pintype "bidirectional"))
      (node (ref "U2") (pin "18") (pinfunction "GND_18") (pintype "bidirectional"))
      (node (ref "U3") (pin "1") (pinfunction "CLKIN_1") (pintype "bidirectional"))
      (node (ref "U3") (pin "11") (pinfunction "FSYNC_11") (pintype "bidirectional"))
      (node (ref "U3") (pin "18") (pinfunction "GND_18") (pintype "bidirectional"))
      (node (ref "U3") (pin "9") (pinfunction "AD0_9") (pintype "bidirectional"))
      (node (ref "U8") (pin "1") (pinfunction "CLKIN_1") (pintype "bidirectional"))
      (node (ref "U8") (pin "11") (pinfunction "FSYNC_11") (pintype "bidirectional"))
      (node (ref "U8") (pin "18") (pinfunction "GND_18") (pintype "bidirectional"))
      (node (ref "U9") (pin "21") (pinfunction "AGND_21") (pintype "bidirectional"))
      (node (ref "U9") (pin "3") (pinfunction "GND_3") (pintype "bidirectional"))
      (node (ref "U9") (pin "5") (pinfunction "GND_5") (pintype "bidirectional"))
      (node (ref "X1") (pin "5") (pinfunction "5_5") (pintype "input"))
    )
    (net (code "5") (name "MISO") (class "Default")
      (node (ref "SV4") (pin "1") (pinfunction "1_1") (pintype "passive"))
      (node (ref "U$1") (pin "P$26") (pinfunction "SDO_G_P$26") (pintype "bidirectional"))
      (node (ref "U$1") (pin "P$27") (pinfunction "SDO_A_P$27") (pintype "bidirectional"))
      (node (ref "U$2") (pin "P$26") (pinfunction "SDO_G_P$26") (pintype "bidirectional"))
      (node (ref "U$2") (pin "P$27") (pinfunction "SDO_A_P$27") (pintype "bidirectional"))
      (node (ref "U$3") (pin "P$26") (pinfunction "SDO_G_P$26") (pintype "bidirectional"))
      (node (ref "U$3") (pin "P$27") (pinfunction "SDO_A_P$27") (pintype "bidirectional"))
      (node (ref "U$4") (pin "P$26") (pinfunction "SDO_G_P$26") (pintype "bidirectional"))
      (node (ref "U$4") (pin "P$27") (pinfunction "SDO_A_P$27") (pintype "bidirectional"))
      (node (ref "U9") (pin "16") (pinfunction "PB4(MISO)_16") (pintype "bidirectional"))
    )
    (net (code "6") (name "MOSI") (class "Default")
      (node (ref "SV4") (pin "4") (pinfunction "4_4") (pintype "passive"))
      (node (ref "U$1") (pin "P$28") (pinfunction "SDA_A/G_P$28") (pintype "bidirectional"))
      (node (ref "U$2") (pin "P$28") (pinfunction "SDA_A/G_P$28") (pintype "bidirectional"))
      (node (ref "U$3") (pin "P$28") (pinfunction "SDA_A/G_P$28") (pintype "bidirectional"))
      (node (ref "U$4") (pin "P$28") (pinfunction "SDA_A/G_P$28") (pintype "bidirectional"))
      (node (ref "U9") (pin "15") (pinfunction "PB3(MOSI/OC2)_15") (pintype "bidirectional"))
    )
    (net (code "7") (name "N$16") (class "Default")
      (node (ref "SV1") (pin "7") (pinfunction "7_7") (pintype "passive"))
      (node (ref "U9") (pin "19") (pinfunction "ADC6_19") (pintype "bidirectional"))
    )
    (net (code "8") (name "N$17") (class "Default")
      (node (ref "SV1") (pin "8") (pinfunction "8_8") (pintype "passive"))
      (node (ref "U9") (pin "22") (pinfunction "ADC7_22") (pintype "bidirectional"))
    )
    (net (code "9") (name "Net-(C83-Pad2)") (class "Default")
      (node (ref "C83") (pin "2") (pinfunction "2_2") (pintype "passive"))
      (node (ref "L2") (pin "1") (pinfunction "1_1") (pintype "passive"))
      (node (ref "X1") (pin "1") (pinfunction "1_1") (pintype "input"))
    )
    (net (code "10") (name "Net-(IC3-CBUS0)") (class "Default")
      (node (ref "IC3") (pin "23") (pinfunction "CBUS0_23") (pintype "bidirectional"))
      (node (ref "LED2") (pin "C") (pinfunction "C_C") (pintype "passive"))
    )
    (net (code "11") (name "Net-(IC3-CBUS1)") (class "Default")
      (node (ref "IC3") (pin "22") (pinfunction "CBUS1_22") (pintype "bidirectional"))
      (node (ref "LED3") (pin "C") (pinfunction "C_C") (pintype "passive"))
    )
    (net (code "12") (name "Net-(IC3-CBUS3)") (class "Default")
      (node (ref "IC3") (pin "14") (pinfunction "CBUS3_14") (pintype "bidirectional"))
      (node (ref "R1") (pin "2") (pinfunction "2_2") (pintype "passive"))
    )
    (net (code "13") (name "Net-(IC3-RXD)") (class "Default")
      (node (ref "IC3") (pin "5") (pinfunction "RXD_5") (pintype "input"))
      (node (ref "R11") (pin "2") (pinfunction "2_2") (pintype "passive"))
    )
    (net (code "14") (name "Net-(IC3-TXD)") (class "Default")
      (node (ref "IC3") (pin "1") (pinfunction "TXD_1") (pintype "output"))
      (node (ref "R10") (pin "2") (pinfunction "2_2") (pintype "passive"))
    )
    (net (code "15") (name "Net-(IC3-USBDM)") (class "Default")
      (node (ref "IC3") (pin "16") (pinfunction "USBDM_16") (pintype "bidirectional"))
      (node (ref "X1") (pin "2") (pinfunction "2_2") (pintype "input"))
    )
    (net (code "16") (name "Net-(IC3-USBDP)") (class "Default")
      (node (ref "IC3") (pin "15") (pinfunction "USBDP_15") (pintype "bidirectional"))
      (node (ref "X1") (pin "3") (pinfunction "3_3") (pintype "input"))
    )
    (net (code "17") (name "Net-(IC3-~{CTS})") (class "Default")
      (node (ref "IC3") (pin "11") (pinfunction "~{CTS}_11") (pintype "input"))
      (node (ref "SV5") (pin "1") (pinfunction "1_1") (pintype "passive"))
    )
    (net (code "18") (name "Net-(IC3-~{DCD})") (class "Default")
      (node (ref "IC3") (pin "10") (pinfunction "~{DCD}_10") (pintype "input"))
      (node (ref "SV5") (pin "3") (pinfunction "3_3") (pintype "passive"))
    )
    (net (code "19") (name "Net-(IC3-~{DSR})") (class "Default")
      (node (ref "IC3") (pin "9") (pinfunction "~{DSR}_9") (pintype "input"))
      (node (ref "SV5") (pin "2") (pinfunction "2_2") (pintype "passive"))
    )
    (net (code "20") (name "Net-(IC3-~{DTR})") (class "Default")
      (node (ref "C78") (pin "1") (pinfunction "1_1") (pintype "passive"))
      (node (ref "IC3") (pin "2") (pinfunction "~{DTR}_2") (pintype "output"))
    )
    (net (code "21") (name "Net-(IC3-~{RI})") (class "Default")
      (node (ref "IC3") (pin "6") (pinfunction "~{RI}_6") (pintype "input"))
      (node (ref "SV5") (pin "4") (pinfunction "4_4") (pintype "passive"))
    )
    (net (code "22") (name "Net-(LED1-PadA)") (class "Default")
      (node (ref "LED1") (pin "A") (pinfunction "A_A") (pintype "passive"))
      (node (ref "R4") (pin "1") (pinfunction "1_1") (pintype "passive"))
    )
    (net (code "23") (name "Net-(LED2-PadA)") (class "Default")
      (node (ref "LED2") (pin "A") (pinfunction "A_A") (pintype "passive"))
      (node (ref "R29") (pin "2") (pinfunction "2_2") (pintype "passive"))
    )
    (net (code "24") (name "Net-(LED3-PadA)") (class "Default")
      (node (ref "LED3") (pin "A") (pinfunction "A_A") (pintype "passive"))
      (node (ref "R30") (pin "2") (pinfunction "2_2") (pintype "passive"))
    )
    (net (code "25") (name "Net-(U$1-CAP)") (class "Default")
      (node (ref "C3") (pin "1") (pinfunction "1_1") (pintype "passive"))
      (node (ref "U$1") (pin "P$15") (pinfunction "CAP_P$15") (pintype "bidirectional"))
    )
    (net (code "26") (name "Net-(U$2-CAP)") (class "Default")
      (node (ref "C10") (pin "1") (pinfunction "1_1") (pintype "passive"))
      (node (ref "U$2") (pin "P$15") (pinfunction "CAP_P$15") (pintype "bidirectional"))
    )
    (net (code "27") (name "Net-(U$3-CAP)") (class "Default")
      (node (ref "C14") (pin "1") (pinfunction "1_1") (pintype "passive"))
      (node (ref "U$3") (pin "P$15") (pinfunction "CAP_P$15") (pintype "bidirectional"))
    )
    (net (code "28") (name "Net-(U$4-CAP)") (class "Default")
      (node (ref "C18") (pin "1") (pinfunction "1_1") (pintype "passive"))
      (node (ref "U$4") (pin "P$15") (pinfunction "CAP_P$15") (pintype "bidirectional"))
    )
    (net (code "29") (name "Net-(U1-CPOUT)") (class "Default")
      (node (ref "C21") (pin "2") (pinfunction "2_2") (pintype "passive"))
      (node (ref "U1") (pin "20") (pinfunction "CPOUT_20") (pintype "bidirectional"))
    )
    (net (code "30") (name "Net-(U1-REGOUT)") (class "Default")
      (node (ref "C20") (pin "2") (pinfunction "2_2") (pintype "passive"))
      (node (ref "U1") (pin "10") (pinfunction "REGOUT_10") (pintype "bidirectional"))
    )
    (net (code "31") (name "Net-(U2-CPOUT)") (class "Default")
      (node (ref "C26") (pin "2") (pinfunction "2_2") (pintype "passive"))
      (node (ref "U2") (pin "20") (pinfunction "CPOUT_20") (pintype "bidirectional"))
    )
    (net (code "32") (name "Net-(U2-REGOUT)") (class "Default")
      (node (ref "C25") (pin "2") (pinfunction "2_2") (pintype "passive"))
      (node (ref "U2") (pin "10") (pinfunction "REGOUT_10") (pintype "bidirectional"))
    )
    (net (code "33") (name "Net-(U3-CPOUT)") (class "Default")
      (node (ref "C30") (pin "2") (pinfunction "2_2") (pintype "passive"))
      (node (ref "U3") (pin "20") (pinfunction "CPOUT_20") (pintype "bidirectional"))
    )
    (net (code "34") (name "Net-(U3-REGOUT)") (class "Default")
      (node (ref "C29") (pin "2") (pinfunction "2_2") (pintype "passive"))
      (node (ref "U3") (pin "10") (pinfunction "REGOUT_10") (pintype "bidirectional"))
    )
    (net (code "35") (name "Net-(U8-CPOUT)") (class "Default")
      (node (ref "C71") (pin "2") (pinfunction "2_2") (pintype "passive"))
      (node (ref "U8") (pin "20") (pinfunction "CPOUT_20") (pintype "bidirectional"))
    )
    (net (code "36") (name "Net-(U8-REGOUT)") (class "Default")
      (node (ref "C70") (pin "2") (pinfunction "2_2") (pintype "passive"))
      (node (ref "U8") (pin "10") (pinfunction "REGOUT_10") (pintype "bidirectional"))
    )
    (net (code "37") (name "Net-(U9-PB6(XTAL1{slash}TOSC1))") (class "Default")
      (node (ref "C24") (pin "2") (pinfunction "2_2") (pintype "passive"))
      (node (ref "U9") (pin "7") (pinfunction "PB6(XTAL1/TOSC1)_7") (pintype "bidirectional"))
      (node (ref "Y1") (pin "2") (pinfunction "2_2") (pintype "passive"))
    )
    (net (code "38") (name "Net-(U9-PB7(XTAL2{slash}TOSC2))") (class "Default")
      (node (ref "C74") (pin "2") (pinfunction "2_2") (pintype "passive"))
      (node (ref "U9") (pin "8") (pinfunction "PB7(XTAL2/TOSC2)_8") (pintype "bidirectional"))
      (node (ref "Y1") (pin "1") (pinfunction "1_1") (pintype "passive"))
    )
    (net (code "39") (name "Net-(U10-BP)") (class "Default")
      (node (ref "C34") (pin "2") (pinfunction "2_2") (pintype "passive"))
      (node (ref "U10") (pin "4") (pinfunction "BP_4") (pintype "input"))
    )
    (net (code "40") (name "RESET") (class "Default")
      (node (ref "C78") (pin "2") (pinfunction "2_2") (pintype "passive"))
      (node (ref "R9") (pin "1") (pinfunction "1_1") (pintype "passive"))
      (node (ref "SV4") (pin "5") (pinfunction "5_5") (pintype "passive"))
      (node (ref "U9") (pin "29") (pinfunction "PC6(/RESET)_29") (pintype "bidirectional"))
    )
    (net (code "41") (name "RXD") (class "Default")
      (node (ref "R10") (pin "1") (pinfunction "1_1") (pintype "passive"))
      (node (ref "SV2") (pin "1") (pinfunction "1_1") (pintype "passive"))
      (node (ref "U9") (pin "30") (pinfunction "PD0(RXD)_30") (pintype "bidirectional"))
    )
    (net (code "42") (name "SCL") (class "Default")
      (node (ref "SV1") (pin "6") (pinfunction "6_6") (pintype "passive"))
      (node (ref "U$5") (pin "P$14") (pinfunction "SCL_P$14") (pintype "bidirectional"))
      (node (ref "U9") (pin "28") (pinfunction "PC5(ADC5/SCL)_28") (pintype "bidirectional"))
    )
    (net (code "43") (name "SCLK") (class "Default")
      (node (ref "SV4") (pin "3") (pinfunction "3_3") (pintype "passive"))
      (node (ref "U$1") (pin "P$24") (pinfunction "SCL_A/G_P$24") (pintype "bidirectional"))
      (node (ref "U$2") (pin "P$24") (pinfunction "SCL_A/G_P$24") (pintype "bidirectional"))
      (node (ref "U$3") (pin "P$24") (pinfunction "SCL_A/G_P$24") (pintype "bidirectional"))
      (node (ref "U$4") (pin "P$24") (pinfunction "SCL_A/G_P$24") (pintype "bidirectional"))
      (node (ref "U9") (pin "17") (pinfunction "PB5(SCK)_17") (pintype "bidirectional"))
    )
    (net (code "44") (name "SCL_0") (class "Default")
      (node (ref "R2") (pin "1") (pinfunction "1_1") (pintype "passive"))
      (node (ref "U$5") (pin "P$5") (pinfunction "SC0_P$5") (pintype "bidirectional"))
      (node (ref "U1") (pin "23") (pinfunction "SCL_23") (pintype "bidirectional"))
      (node (ref "U8") (pin "23") (pinfunction "SCL_23") (pintype "bidirectional"))
    )
    (net (code "45") (name "SCL_1") (class "Default")
      (node (ref "R6") (pin "2") (pinfunction "2_2") (pintype "passive"))
      (node (ref "U$5") (pin "P$7") (pinfunction "SC1_P$7") (pintype "bidirectional"))
      (node (ref "U2") (pin "23") (pinfunction "SCL_23") (pintype "bidirectional"))
      (node (ref "U3") (pin "23") (pinfunction "SCL_23") (pintype "bidirectional"))
    )
    (net (code "46") (name "SDA") (class "Default")
      (node (ref "SV1") (pin "5") (pinfunction "5_5") (pintype "passive"))
      (node (ref "U$5") (pin "P$15") (pinfunction "SDA_P$15") (pintype "bidirectional"))
      (node (ref "U9") (pin "27") (pinfunction "PC4(ADC4/SDA)_27") (pintype "bidirectional"))
    )
    (net (code "47") (name "SDA_0") (class "Default")
      (node (ref "R3") (pin "1") (pinfunction "1_1") (pintype "passive"))
      (node (ref "U$5") (pin "P$4") (pinfunction "SD0_P$4") (pintype "bidirectional"))
      (node (ref "U1") (pin "24") (pinfunction "SDA_24") (pintype "bidirectional"))
      (node (ref "U8") (pin "24") (pinfunction "SDA_24") (pintype "bidirectional"))
    )
    (net (code "48") (name "SDA_1") (class "Default")
      (node (ref "R5") (pin "2") (pinfunction "2_2") (pintype "passive"))
      (node (ref "U$5") (pin "P$6") (pinfunction "SD1_P$6") (pintype "bidirectional"))
      (node (ref "U2") (pin "24") (pinfunction "SDA_24") (pintype "bidirectional"))
      (node (ref "U3") (pin "24") (pinfunction "SDA_24") (pintype "bidirectional"))
    )
    (net (code "49") (name "TXD") (class "Default")
      (node (ref "R11") (pin "1") (pinfunction "1_1") (pintype "passive"))
      (node (ref "SV2") (pin "2") (pinfunction "2_2") (pintype "passive"))
      (node (ref "U9") (pin "31") (pinfunction "PD1(TXD)_31") (pintype "bidirectional"))
    )
    (net (code "50") (name "unconnected-(IC3-3V3OUT-Pad17)") (class "Default")
      (node (ref "IC3") (pin "17") (pinfunction "3V3OUT_17") (pintype "output"))
    )
    (net (code "51") (name "unconnected-(IC3-CBUS2-Pad13)") (class "Default")
      (node (ref "IC3") (pin "13") (pinfunction "CBUS2_13") (pintype "bidirectional"))
    )
    (net (code "52") (name "unconnected-(IC3-CBUS4-Pad12)") (class "Default")
      (node (ref "IC3") (pin "12") (pinfunction "CBUS4_12") (pintype "bidirectional"))
    )
    (net (code "53") (name "unconnected-(IC3-OSCI-Pad27)") (class "Default")
      (node (ref "IC3") (pin "27") (pinfunction "OSCI_27") (pintype "input"))
    )
    (net (code "54") (name "unconnected-(IC3-OSCO-Pad28)") (class "Default")
      (node (ref "IC3") (pin "28") (pinfunction "OSCO_28") (pintype "output"))
    )
    (net (code "55") (name "unconnected-(IC3-~{RTS}-Pad3)") (class "Default")
      (node (ref "IC3") (pin "3") (pinfunction "~{RTS}_3") (pintype "output"))
    )
    (net (code "56") (name "unconnected-(U$1-DEN_G-PadP$16)") (class "Default")
      (node (ref "U$1") (pin "P$16") (pinfunction "DEN_G_P$16") (pintype "bidirectional"))
    )
    (net (code "57") (name "unconnected-(U$1-DRDY_G{slash}INT2_G-PadP$17)") (class "Default")
      (node (ref "U$1") (pin "P$17") (pinfunction "DRDY_G/INT2_G_P$17") (pintype "bidirectional"))
    )
    (net (code "58") (name "unconnected-(U$1-INT1_A-PadP$20)") (class "Default")
      (node (ref "U$1") (pin "P$20") (pinfunction "INT1_A_P$20") (pintype "bidirectional"))
    )
    (net (code "59") (name "unconnected-(U$1-INT1_G-PadP$18)") (class "Default")
      (node (ref "U$1") (pin "P$18") (pinfunction "INT1_G_P$18") (pintype "bidirectional"))
    )
    (net (code "60") (name "unconnected-(U$1-INT2_A-PadP$19)") (class "Default")
      (node (ref "U$1") (pin "P$19") (pinfunction "INT2_A_P$19") (pintype "bidirectional"))
    )
    (net (code "61") (name "unconnected-(U$2-DEN_G-PadP$16)") (class "Default")
      (node (ref "U$2") (pin "P$16") (pinfunction "DEN_G_P$16") (pintype "bidirectional"))
    )
    (net (code "62") (name "unconnected-(U$2-DRDY_G{slash}INT2_G-PadP$17)") (class "Default")
      (node (ref "U$2") (pin "P$17") (pinfunction "DRDY_G/INT2_G_P$17") (pintype "bidirectional"))
    )
    (net (code "63") (name "unconnected-(U$2-INT1_A-PadP$20)") (class "Default")
      (node (ref "U$2") (pin "P$20") (pinfunction "INT1_A_P$20") (pintype "bidirectional"))
    )
    (net (code "64") (name "unconnected-(U$2-INT1_G-PadP$18)") (class "Default")
      (node (ref "U$2") (pin "P$18") (pinfunction "INT1_G_P$18") (pintype "bidirectional"))
    )
    (net (code "65") (name "unconnected-(U$2-INT2_A-PadP$19)") (class "Default")
      (node (ref "U$2") (pin "P$19") (pinfunction "INT2_A_P$19") (pintype "bidirectional"))
    )
    (net (code "66") (name "unconnected-(U$3-DEN_G-PadP$16)") (class "Default")
      (node (ref "U$3") (pin "P$16") (pinfunction "DEN_G_P$16") (pintype "bidirectional"))
    )
    (net (code "67") (name "unconnected-(U$3-DRDY_G{slash}INT2_G-PadP$17)") (class "Default")
      (node (ref "U$3") (pin "P$17") (pinfunction "DRDY_G/INT2_G_P$17") (pintype "bidirectional"))
    )
    (net (code "68") (name "unconnected-(U$3-INT1_A-PadP$20)") (class "Default")
      (node (ref "U$3") (pin "P$20") (pinfunction "INT1_A_P$20") (pintype "bidirectional"))
    )
    (net (code "69") (name "unconnected-(U$3-INT1_G-PadP$18)") (class "Default")
      (node (ref "U$3") (pin "P$18") (pinfunction "INT1_G_P$18") (pintype "bidirectional"))
    )
    (net (code "70") (name "unconnected-(U$3-INT2_A-PadP$19)") (class "Default")
      (node (ref "U$3") (pin "P$19") (pinfunction "INT2_A_P$19") (pintype "bidirectional"))
    )
    (net (code "71") (name "unconnected-(U$4-DEN_G-PadP$16)") (class "Default")
      (node (ref "U$4") (pin "P$16") (pinfunction "DEN_G_P$16") (pintype "bidirectional"))
    )
    (net (code "72") (name "unconnected-(U$4-DRDY_G{slash}INT2_G-PadP$17)") (class "Default")
      (node (ref "U$4") (pin "P$17") (pinfunction "DRDY_G/INT2_G_P$17") (pintype "bidirectional"))
    )
    (net (code "73") (name "unconnected-(U$4-INT1_A-PadP$20)") (class "Default")
      (node (ref "U$4") (pin "P$20") (pinfunction "INT1_A_P$20") (pintype "bidirectional"))
    )
    (net (code "74") (name "unconnected-(U$4-INT1_G-PadP$18)") (class "Default")
      (node (ref "U$4") (pin "P$18") (pinfunction "INT1_G_P$18") (pintype "bidirectional"))
    )
    (net (code "75") (name "unconnected-(U$4-INT2_A-PadP$19)") (class "Default")
      (node (ref "U$4") (pin "P$19") (pinfunction "INT2_A_P$19") (pintype "bidirectional"))
    )
    (net (code "76") (name "unconnected-(U$5-SC2-PadP$10)") (class "Default")
      (node (ref "U$5") (pin "P$10") (pinfunction "SC2_P$10") (pintype "bidirectional"))
    )
    (net (code "77") (name "unconnected-(U$5-SC3-PadP$12)") (class "Default")
      (node (ref "U$5") (pin "P$12") (pinfunction "SC3_P$12") (pintype "bidirectional"))
    )
    (net (code "78") (name "unconnected-(U$5-SD2-PadP$9)") (class "Default")
      (node (ref "U$5") (pin "P$9") (pinfunction "SD2_P$9") (pintype "bidirectional"))
    )
    (net (code "79") (name "unconnected-(U$5-SD3-PadP$11)") (class "Default")
      (node (ref "U$5") (pin "P$11") (pinfunction "SD3_P$11") (pintype "bidirectional"))
    )
    (net (code "80") (name "unconnected-(U1-AUX_CL-Pad7)") (class "Default")
      (node (ref "U1") (pin "7") (pinfunction "AUX_CL_7") (pintype "bidirectional"))
    )
    (net (code "81") (name "unconnected-(U1-AUX_DA-Pad6)") (class "Default")
      (node (ref "U1") (pin "6") (pinfunction "AUX_DA_6") (pintype "bidirectional"))
    )
    (net (code "82") (name "unconnected-(U1-INT-Pad12)") (class "Default")
      (node (ref "U1") (pin "12") (pinfunction "INT_12") (pintype "bidirectional"))
    )
    (net (code "83") (name "unconnected-(U2-AUX_CL-Pad7)") (class "Default")
      (node (ref "U2") (pin "7") (pinfunction "AUX_CL_7") (pintype "bidirectional"))
    )
    (net (code "84") (name "unconnected-(U2-AUX_DA-Pad6)") (class "Default")
      (node (ref "U2") (pin "6") (pinfunction "AUX_DA_6") (pintype "bidirectional"))
    )
    (net (code "85") (name "unconnected-(U2-INT-Pad12)") (class "Default")
      (node (ref "U2") (pin "12") (pinfunction "INT_12") (pintype "bidirectional"))
    )
    (net (code "86") (name "unconnected-(U3-AUX_CL-Pad7)") (class "Default")
      (node (ref "U3") (pin "7") (pinfunction "AUX_CL_7") (pintype "bidirectional"))
    )
    (net (code "87") (name "unconnected-(U3-AUX_DA-Pad6)") (class "Default")
      (node (ref "U3") (pin "6") (pinfunction "AUX_DA_6") (pintype "bidirectional"))
    )
    (net (code "88") (name "unconnected-(U3-INT-Pad12)") (class "Default")
      (node (ref "U3") (pin "12") (pinfunction "INT_12") (pintype "bidirectional"))
    )
    (net (code "89") (name "unconnected-(U8-AUX_CL-Pad7)") (class "Default")
      (node (ref "U8") (pin "7") (pinfunction "AUX_CL_7") (pintype "bidirectional"))
    )
    (net (code "90") (name "unconnected-(U8-AUX_DA-Pad6)") (class "Default")
      (node (ref "U8") (pin "6") (pinfunction "AUX_DA_6") (pintype "bidirectional"))
    )
    (net (code "91") (name "unconnected-(U8-INT-Pad12)") (class "Default")
      (node (ref "U8") (pin "12") (pinfunction "INT_12") (pintype "bidirectional"))
    )
    (net (code "92") (name "unconnected-(U9-PB2(SS{slash}OC1B)-Pad14)") (class "Default")
      (node (ref "U9") (pin "14") (pinfunction "PB2(SS/OC1B)_14") (pintype "bidirectional"))
    )
    (net (code "93") (name "unconnected-(U9-PD4(XCK{slash}T0)-Pad2)") (class "Default")
      (node (ref "U9") (pin "2") (pinfunction "PD4(XCK/T0)_2") (pintype "bidirectional"))
    )
    (net (code "94") (name "unconnected-(U9-PD5(T1)-Pad9)") (class "Default")
      (node (ref "U9") (pin "9") (pinfunction "PD5(T1)_9") (pintype "bidirectional"))
    )
    (net (code "95") (name "unconnected-(U9-PD6(AIN0)-Pad10)") (class "Default")
      (node (ref "U9") (pin "10") (pinfunction "PD6(AIN0)_10") (pintype "bidirectional"))
    )
    (net (code "96") (name "unconnected-(U9-PD7(AIN1)-Pad11)") (class "Default")
      (node (ref "U9") (pin "11") (pinfunction "PD7(AIN1)_11") (pintype "bidirectional"))
    )
    (net (code "97") (name "unconnected-(X1-Pad4)") (class "Default")
      (node (ref "X1") (pin "4") (pinfunction "4_4") (pintype "input"))
    )
    (net (code "98") (name "~{CS_A0}") (class "Default")
      (node (ref "R13") (pin "1") (pinfunction "1_1") (pintype "passive"))
      (node (ref "SV1") (pin "2") (pinfunction "2_2") (pintype "passive"))
      (node (ref "U$1") (pin "P$23") (pinfunction "~{CS_A}_P$23") (pintype "bidirectional"))
      (node (ref "U9") (pin "24") (pinfunction "PC1(ADC1)_24") (pintype "bidirectional"))
    )
    (net (code "99") (name "~{CS_A1}") (class "Default")
      (node (ref "R8") (pin "1") (pinfunction "1_1") (pintype "passive"))
      (node (ref "SV1") (pin "4") (pinfunction "4_4") (pintype "passive"))
      (node (ref "U$2") (pin "P$23") (pinfunction "~{CS_A}_P$23") (pintype "bidirectional"))
      (node (ref "U9") (pin "26") (pinfunction "PC3(ADC3)_26") (pintype "bidirectional"))
    )
    (net (code "100") (name "~{CS_A2}") (class "Default")
      (node (ref "R17") (pin "1") (pinfunction "1_1") (pintype "passive"))
      (node (ref "U$4") (pin "P$23") (pinfunction "~{CS_A}_P$23") (pintype "bidirectional"))
      (node (ref "U9") (pin "13") (pinfunction "PB1(OC1A)_13") (pintype "bidirectional"))
    )
    (net (code "101") (name "~{CS_A3}") (class "Default")
      (node (ref "R15") (pin "1") (pinfunction "1_1") (pintype "passive"))
      (node (ref "SV2") (pin "4") (pinfunction "4_4") (pintype "passive"))
      (node (ref "U$3") (pin "P$23") (pinfunction "~{CS_A}_P$23") (pintype "bidirectional"))
      (node (ref "U9") (pin "1") (pinfunction "PD3(INT1)_1") (pintype "bidirectional"))
    )
    (net (code "102") (name "~{CS_G0}") (class "Default")
      (node (ref "R12") (pin "1") (pinfunction "1_1") (pintype "passive"))
      (node (ref "SV1") (pin "1") (pinfunction "1_1") (pintype "passive"))
      (node (ref "U$1") (pin "P$22") (pinfunction "~{CS_G}_P$22") (pintype "bidirectional"))
      (node (ref "U9") (pin "23") (pinfunction "PC0(ADC0)_23") (pintype "bidirectional"))
    )
    (net (code "103") (name "~{CS_G1}") (class "Default")
      (node (ref "R7") (pin "1") (pinfunction "1_1") (pintype "passive"))
      (node (ref "SV1") (pin "3") (pinfunction "3_3") (pintype "passive"))
      (node (ref "U$2") (pin "P$22") (pinfunction "~{CS_G}_P$22") (pintype "bidirectional"))
      (node (ref "U9") (pin "25") (pinfunction "PC2(ADC2)_25") (pintype "bidirectional"))
    )
    (net (code "104") (name "~{CS_G2}") (class "Default")
      (node (ref "R16") (pin "1") (pinfunction "1_1") (pintype "passive"))
      (node (ref "U$4") (pin "P$22") (pinfunction "~{CS_G}_P$22") (pintype "bidirectional"))
      (node (ref "U9") (pin "12") (pinfunction "PB0(ICP)_12") (pintype "bidirectional"))
    )
    (net (code "105") (name "~{CS_G3}") (class "Default")
      (node (ref "R14") (pin "1") (pinfunction "1_1") (pintype "passive"))
      (node (ref "SV2") (pin "3") (pinfunction "3_3") (pintype "passive"))
      (node (ref "U$3") (pin "P$22") (pinfunction "~{CS_G}_P$22") (pintype "bidirectional"))
      (node (ref "U9") (pin "32") (pinfunction "PD2(INT0)_32") (pintype "bidirectional"))
    )
  )
)
